# CEM3360-VCA-IO.net
KiCad netlist of a schematic drawn in EAGLE
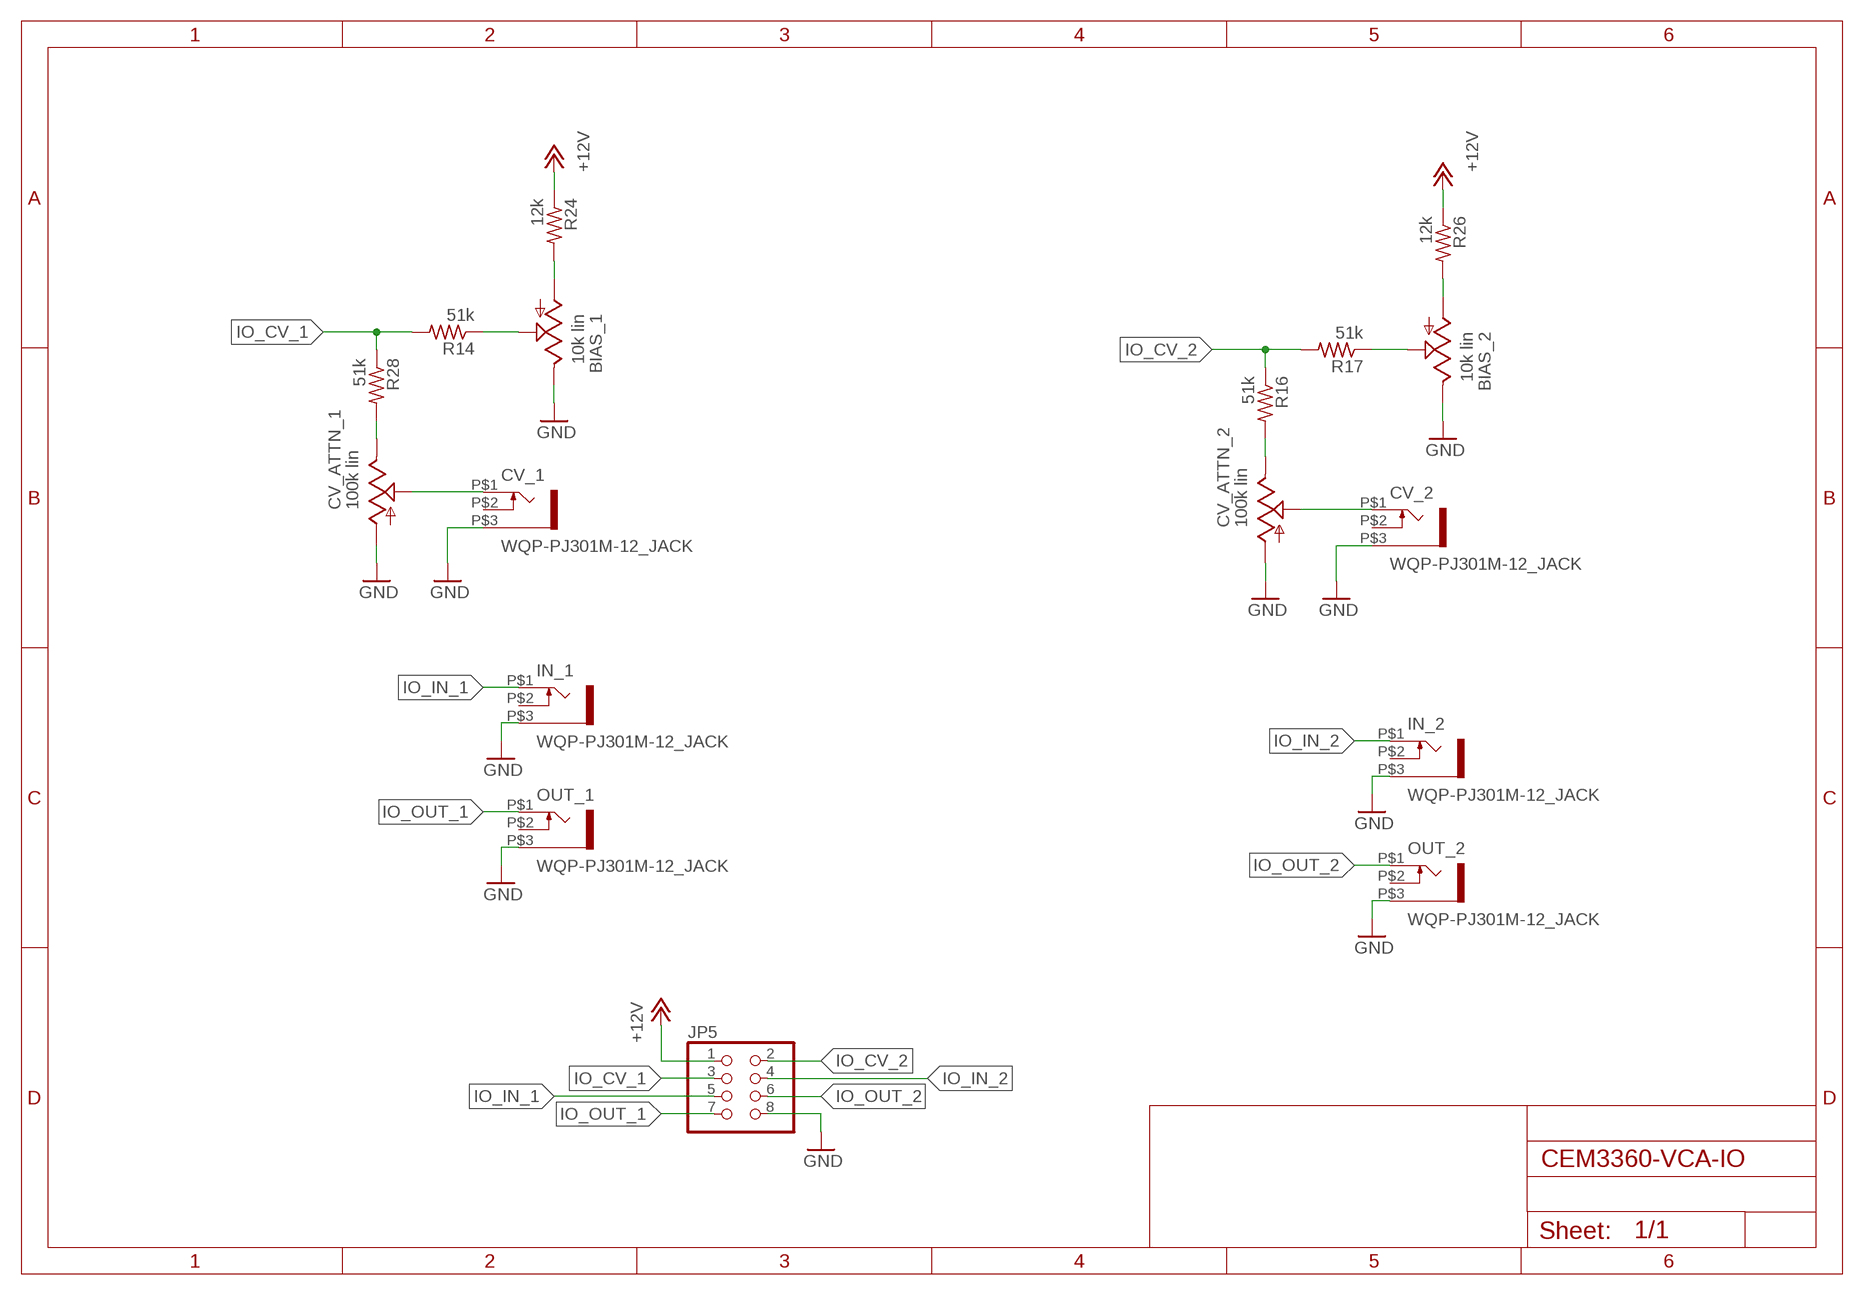
[diagram p0: schematic, sheet 1]

(export (version "E")
  (design (tool "Eeschema 10.0.6"))
  (components
    (comp (ref "BIAS_1")
      (value "10k lin")
      (footprint "eagle-import:EVUF")
      (libsource (lib "eagle-import") (part "ALPHA-9MMA"))
    )
    (comp (ref "BIAS_2")
      (value "10k lin")
      (footprint "eagle-import:EVUF")
      (libsource (lib "eagle-import") (part "ALPHA-9MMA"))
    )
    (comp (ref "CV_1")
      (value "WQP-PJ301M-12_JACK")
      (footprint "eagle-import:WQP-PJ301M-12_JACK")
      (libsource (lib "eagle-import") (part "WQP-PJ301M-12_JACK"))
    )
    (comp (ref "CV_2")
      (value "WQP-PJ301M-12_JACK")
      (footprint "eagle-import:WQP-PJ301M-12_JACK")
      (libsource (lib "eagle-import") (part "WQP-PJ301M-12_JACK"))
    )
    (comp (ref "CV_ATTN_1")
      (value "100k lin")
      (footprint "eagle-import:EVUF")
      (libsource (lib "eagle-import") (part "ALPHA-9MMA"))
    )
    (comp (ref "CV_ATTN_2")
      (value "100k lin")
      (footprint "eagle-import:EVUF")
      (libsource (lib "eagle-import") (part "ALPHA-9MMA"))
    )
    (comp (ref "IN_1")
      (value "WQP-PJ301M-12_JACK")
      (footprint "eagle-import:WQP-PJ301M-12_JACK")
      (libsource (lib "eagle-import") (part "WQP-PJ301M-12_JACK"))
    )
    (comp (ref "IN_2")
      (value "WQP-PJ301M-12_JACK")
      (footprint "eagle-import:WQP-PJ301M-12_JACK")
      (libsource (lib "eagle-import") (part "WQP-PJ301M-12_JACK"))
    )
    (comp (ref "JP5")
      (value "PINHD-2X4")
      (footprint "eagle-import:2X04")
      (libsource (lib "eagle-import") (part "PINHD-2X4"))
    )
    (comp (ref "OUT_1")
      (value "WQP-PJ301M-12_JACK")
      (footprint "eagle-import:WQP-PJ301M-12_JACK")
      (libsource (lib "eagle-import") (part "WQP-PJ301M-12_JACK"))
    )
    (comp (ref "OUT_2")
      (value "WQP-PJ301M-12_JACK")
      (footprint "eagle-import:WQP-PJ301M-12_JACK")
      (libsource (lib "eagle-import") (part "WQP-PJ301M-12_JACK"))
    )
    (comp (ref "R14")
      (value "51k")
      (footprint "eagle-import:0207_7")
      (libsource (lib "eagle-import") (part "R-US_0207/7"))
    )
    (comp (ref "R16")
      (value "51k")
      (footprint "eagle-import:0207_7")
      (libsource (lib "eagle-import") (part "R-US_0207/7"))
    )
    (comp (ref "R17")
      (value "51k")
      (footprint "eagle-import:0207_7")
      (libsource (lib "eagle-import") (part "R-US_0207/7"))
    )
    (comp (ref "R24")
      (value "12k")
      (footprint "eagle-import:0207_7")
      (libsource (lib "eagle-import") (part "R-US_0207/7"))
    )
    (comp (ref "R26")
      (value "12k")
      (footprint "eagle-import:0207_7")
      (libsource (lib "eagle-import") (part "R-US_0207/7"))
    )
    (comp (ref "R28")
      (value "51k")
      (footprint "eagle-import:0207_7")
      (libsource (lib "eagle-import") (part "R-US_0207/7"))
    )
  )
  (nets
    (net (code "1") (name "+12V") (class "Default")
      (node (ref "JP5") (pin "1") (pinfunction "1_1") (pintype "passive"))
      (node (ref "R24") (pin "1") (pinfunction "1_1") (pintype "passive"))
      (node (ref "R26") (pin "1") (pinfunction "1_1") (pintype "passive"))
    )
    (net (code "2") (name "GND") (class "Default")
      (node (ref "BIAS_1") (pin "3") (pinfunction "E_3") (pintype "passive"))
      (node (ref "BIAS_2") (pin "3") (pinfunction "E_3") (pintype "passive"))
      (node (ref "CV_1") (pin "P$3") (pinfunction "1_P$3") (pintype "passive"))
      (node (ref "CV_2") (pin "P$3") (pinfunction "1_P$3") (pintype "passive"))
      (node (ref "CV_ATTN_1") (pin "1") (pinfunction "A_1") (pintype "passive"))
      (node (ref "CV_ATTN_2") (pin "1") (pinfunction "A_1") (pintype "passive"))
      (node (ref "IN_1") (pin "P$3") (pinfunction "1_P$3") (pintype "passive"))
      (node (ref "IN_2") (pin "P$3") (pinfunction "1_P$3") (pintype "passive"))
      (node (ref "JP5") (pin "8") (pinfunction "8_8") (pintype "passive"))
      (node (ref "OUT_1") (pin "P$3") (pinfunction "1_P$3") (pintype "passive"))
      (node (ref "OUT_2") (pin "P$3") (pinfunction "1_P$3") (pintype "passive"))
    )
    (net (code "3") (name "IO_CV_1") (class "Default")
      (node (ref "JP5") (pin "3") (pinfunction "3_3") (pintype "passive"))
      (node (ref "R14") (pin "2") (pinfunction "2_2") (pintype "passive"))
      (node (ref "R28") (pin "1") (pinfunction "1_1") (pintype "passive"))
    )
    (net (code "4") (name "IO_CV_2") (class "Default")
      (node (ref "JP5") (pin "2") (pinfunction "2_2") (pintype "passive"))
      (node (ref "R16") (pin "1") (pinfunction "1_1") (pintype "passive"))
      (node (ref "R17") (pin "2") (pinfunction "2_2") (pintype "passive"))
    )
    (net (code "5") (name "IO_IN_1") (class "Default")
      (node (ref "IN_1") (pin "P$1") (pinfunction "2_P$1") (pintype "passive"))
      (node (ref "JP5") (pin "5") (pinfunction "5_5") (pintype "passive"))
    )
    (net (code "6") (name "IO_IN_2") (class "Default")
      (node (ref "IN_2") (pin "P$1") (pinfunction "2_P$1") (pintype "passive"))
      (node (ref "JP5") (pin "4") (pinfunction "4_4") (pintype "passive"))
    )
    (net (code "7") (name "IO_OUT_1") (class "Default")
      (node (ref "JP5") (pin "7") (pinfunction "7_7") (pintype "passive"))
      (node (ref "OUT_1") (pin "P$1") (pinfunction "2_P$1") (pintype "passive"))
    )
    (net (code "8") (name "IO_OUT_2") (class "Default")
      (node (ref "JP5") (pin "6") (pinfunction "6_6") (pintype "passive"))
      (node (ref "OUT_2") (pin "P$1") (pinfunction "2_P$1") (pintype "passive"))
    )
    (net (code "9") (name "Net-(BIAS_1-A)") (class "Default")
      (node (ref "BIAS_1") (pin "1") (pinfunction "A_1") (pintype "passive"))
      (node (ref "R24") (pin "2") (pinfunction "2_2") (pintype "passive"))
    )
    (net (code "10") (name "Net-(BIAS_1-S)") (class "Default")
      (node (ref "BIAS_1") (pin "2") (pinfunction "S_2") (pintype "passive"))
      (node (ref "R14") (pin "1") (pinfunction "1_1") (pintype "passive"))
    )
    (net (code "11") (name "Net-(BIAS_2-A)") (class "Default")
      (node (ref "BIAS_2") (pin "1") (pinfunction "A_1") (pintype "passive"))
      (node (ref "R26") (pin "2") (pinfunction "2_2") (pintype "passive"))
    )
    (net (code "12") (name "Net-(BIAS_2-S)") (class "Default")
      (node (ref "BIAS_2") (pin "2") (pinfunction "S_2") (pintype "passive"))
      (node (ref "R17") (pin "1") (pinfunction "1_1") (pintype "passive"))
    )
    (net (code "13") (name "Net-(CV_1-2)") (class "Default")
      (node (ref "CV_1") (pin "P$1") (pinfunction "2_P$1") (pintype "passive"))
      (node (ref "CV_ATTN_1") (pin "2") (pinfunction "S_2") (pintype "passive"))
    )
    (net (code "14") (name "Net-(CV_2-2)") (class "Default")
      (node (ref "CV_2") (pin "P$1") (pinfunction "2_P$1") (pintype "passive"))
      (node (ref "CV_ATTN_2") (pin "2") (pinfunction "S_2") (pintype "passive"))
    )
    (net (code "15") (name "Net-(CV_ATTN_1-E)") (class "Default")
      (node (ref "CV_ATTN_1") (pin "3") (pinfunction "E_3") (pintype "passive"))
      (node (ref "R28") (pin "2") (pinfunction "2_2") (pintype "passive"))
    )
    (net (code "16") (name "Net-(CV_ATTN_2-E)") (class "Default")
      (node (ref "CV_ATTN_2") (pin "3") (pinfunction "E_3") (pintype "passive"))
      (node (ref "R16") (pin "2") (pinfunction "2_2") (pintype "passive"))
    )
    (net (code "17") (name "unconnected-(CV_1-3-PadP$2)") (class "Default")
      (node (ref "CV_1") (pin "P$2") (pinfunction "3_P$2") (pintype "passive"))
    )
    (net (code "18") (name "unconnected-(CV_2-3-PadP$2)") (class "Default")
      (node (ref "CV_2") (pin "P$2") (pinfunction "3_P$2") (pintype "passive"))
    )
    (net (code "19") (name "unconnected-(IN_1-3-PadP$2)") (class "Default")
      (node (ref "IN_1") (pin "P$2") (pinfunction "3_P$2") (pintype "passive"))
    )
    (net (code "20") (name "unconnected-(IN_2-3-PadP$2)") (class "Default")
      (node (ref "IN_2") (pin "P$2") (pinfunction "3_P$2") (pintype "passive"))
    )
    (net (code "21") (name "unconnected-(OUT_1-3-PadP$2)") (class "Default")
      (node (ref "OUT_1") (pin "P$2") (pinfunction "3_P$2") (pintype "passive"))
    )
    (net (code "22") (name "unconnected-(OUT_2-3-PadP$2)") (class "Default")
      (node (ref "OUT_2") (pin "P$2") (pinfunction "3_P$2") (pintype "passive"))
    )
  )
)
